# DPad-Buttons.net
KiCad netlist of a schematic drawn in EAGLE
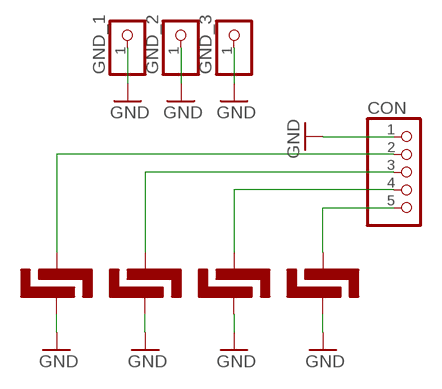
[diagram p0: schematic, sheet 1]

(export (version "E")
  (design (tool "Eeschema 10.0.6"))
  (components
    (comp (ref "BTN1")
      (value "BTN_5MM_LONG")
      (footprint "eagle-import:BTN_5MM_LONG")
      (libsource (lib "eagle-import") (part "BTN_5MM_LONG"))
    )
    (comp (ref "BTN2")
      (value "BTN_5MM_LONG")
      (footprint "eagle-import:BTN_5MM_LONG")
      (libsource (lib "eagle-import") (part "BTN_5MM_LONG"))
    )
    (comp (ref "BTN3")
      (value "BTN_5MM_LONG")
      (footprint "eagle-import:BTN_5MM_LONG")
      (libsource (lib "eagle-import") (part "BTN_5MM_LONG"))
    )
    (comp (ref "BTN4")
      (value "BTN_5MM_LONG")
      (footprint "eagle-import:BTN_5MM_LONG")
      (libsource (lib "eagle-import") (part "BTN_5MM_LONG"))
    )
    (comp (ref "CON")
      (value "PINHD-1X5/90")
      (footprint "eagle-import:1X05_90")
      (libsource (lib "eagle-import") (part "PINHD-1X5/90"))
    )
    (comp (ref "GND_1")
      (value "PINHD-1X1")
      (footprint "eagle-import:1X01")
      (libsource (lib "eagle-import") (part "PINHD-1X1"))
    )
    (comp (ref "GND_2")
      (value "PINHD-1X1")
      (footprint "eagle-import:1X01")
      (libsource (lib "eagle-import") (part "PINHD-1X1"))
    )
    (comp (ref "GND_3")
      (value "PINHD-1X1")
      (footprint "eagle-import:1X01")
      (libsource (lib "eagle-import") (part "PINHD-1X1"))
    )
  )
  (nets
    (net (code "1") (name "GND") (class "Default")
      (node (ref "BTN1") (pin "P$2") (pinfunction "P$2_P$2") (pintype "bidirectional"))
      (node (ref "BTN2") (pin "P$2") (pinfunction "P$2_P$2") (pintype "bidirectional"))
      (node (ref "BTN3") (pin "P$2") (pinfunction "P$2_P$2") (pintype "bidirectional"))
      (node (ref "BTN4") (pin "P$2") (pinfunction "P$2_P$2") (pintype "bidirectional"))
      (node (ref "CON") (pin "1") (pinfunction "1_1") (pintype "passive"))
      (node (ref "GND_1") (pin "1") (pinfunction "1_1") (pintype "passive"))
      (node (ref "GND_2") (pin "1") (pinfunction "1_1") (pintype "passive"))
      (node (ref "GND_3") (pin "1") (pinfunction "1_1") (pintype "passive"))
    )
    (net (code "2") (name "Net-(BTN1-PadP$1)") (class "Default")
      (node (ref "BTN1") (pin "P$1") (pinfunction "P$1_P$1") (pintype "bidirectional"))
      (node (ref "CON") (pin "2") (pinfunction "2_2") (pintype "passive"))
    )
    (net (code "3") (name "Net-(BTN2-PadP$1)") (class "Default")
      (node (ref "BTN2") (pin "P$1") (pinfunction "P$1_P$1") (pintype "bidirectional"))
      (node (ref "CON") (pin "3") (pinfunction "3_3") (pintype "passive"))
    )
    (net (code "4") (name "Net-(BTN3-PadP$1)") (class "Default")
      (node (ref "BTN3") (pin "P$1") (pinfunction "P$1_P$1") (pintype "bidirectional"))
      (node (ref "CON") (pin "4") (pinfunction "4_4") (pintype "passive"))
    )
    (net (code "5") (name "Net-(BTN4-PadP$1)") (class "Default")
      (node (ref "BTN4") (pin "P$1") (pinfunction "P$1_P$1") (pintype "bidirectional"))
      (node (ref "CON") (pin "5") (pinfunction "5_5") (pintype "passive"))
    )
  )
)
